# HUB-USB.net
KiCad netlist of a schematic drawn in Altium Designer
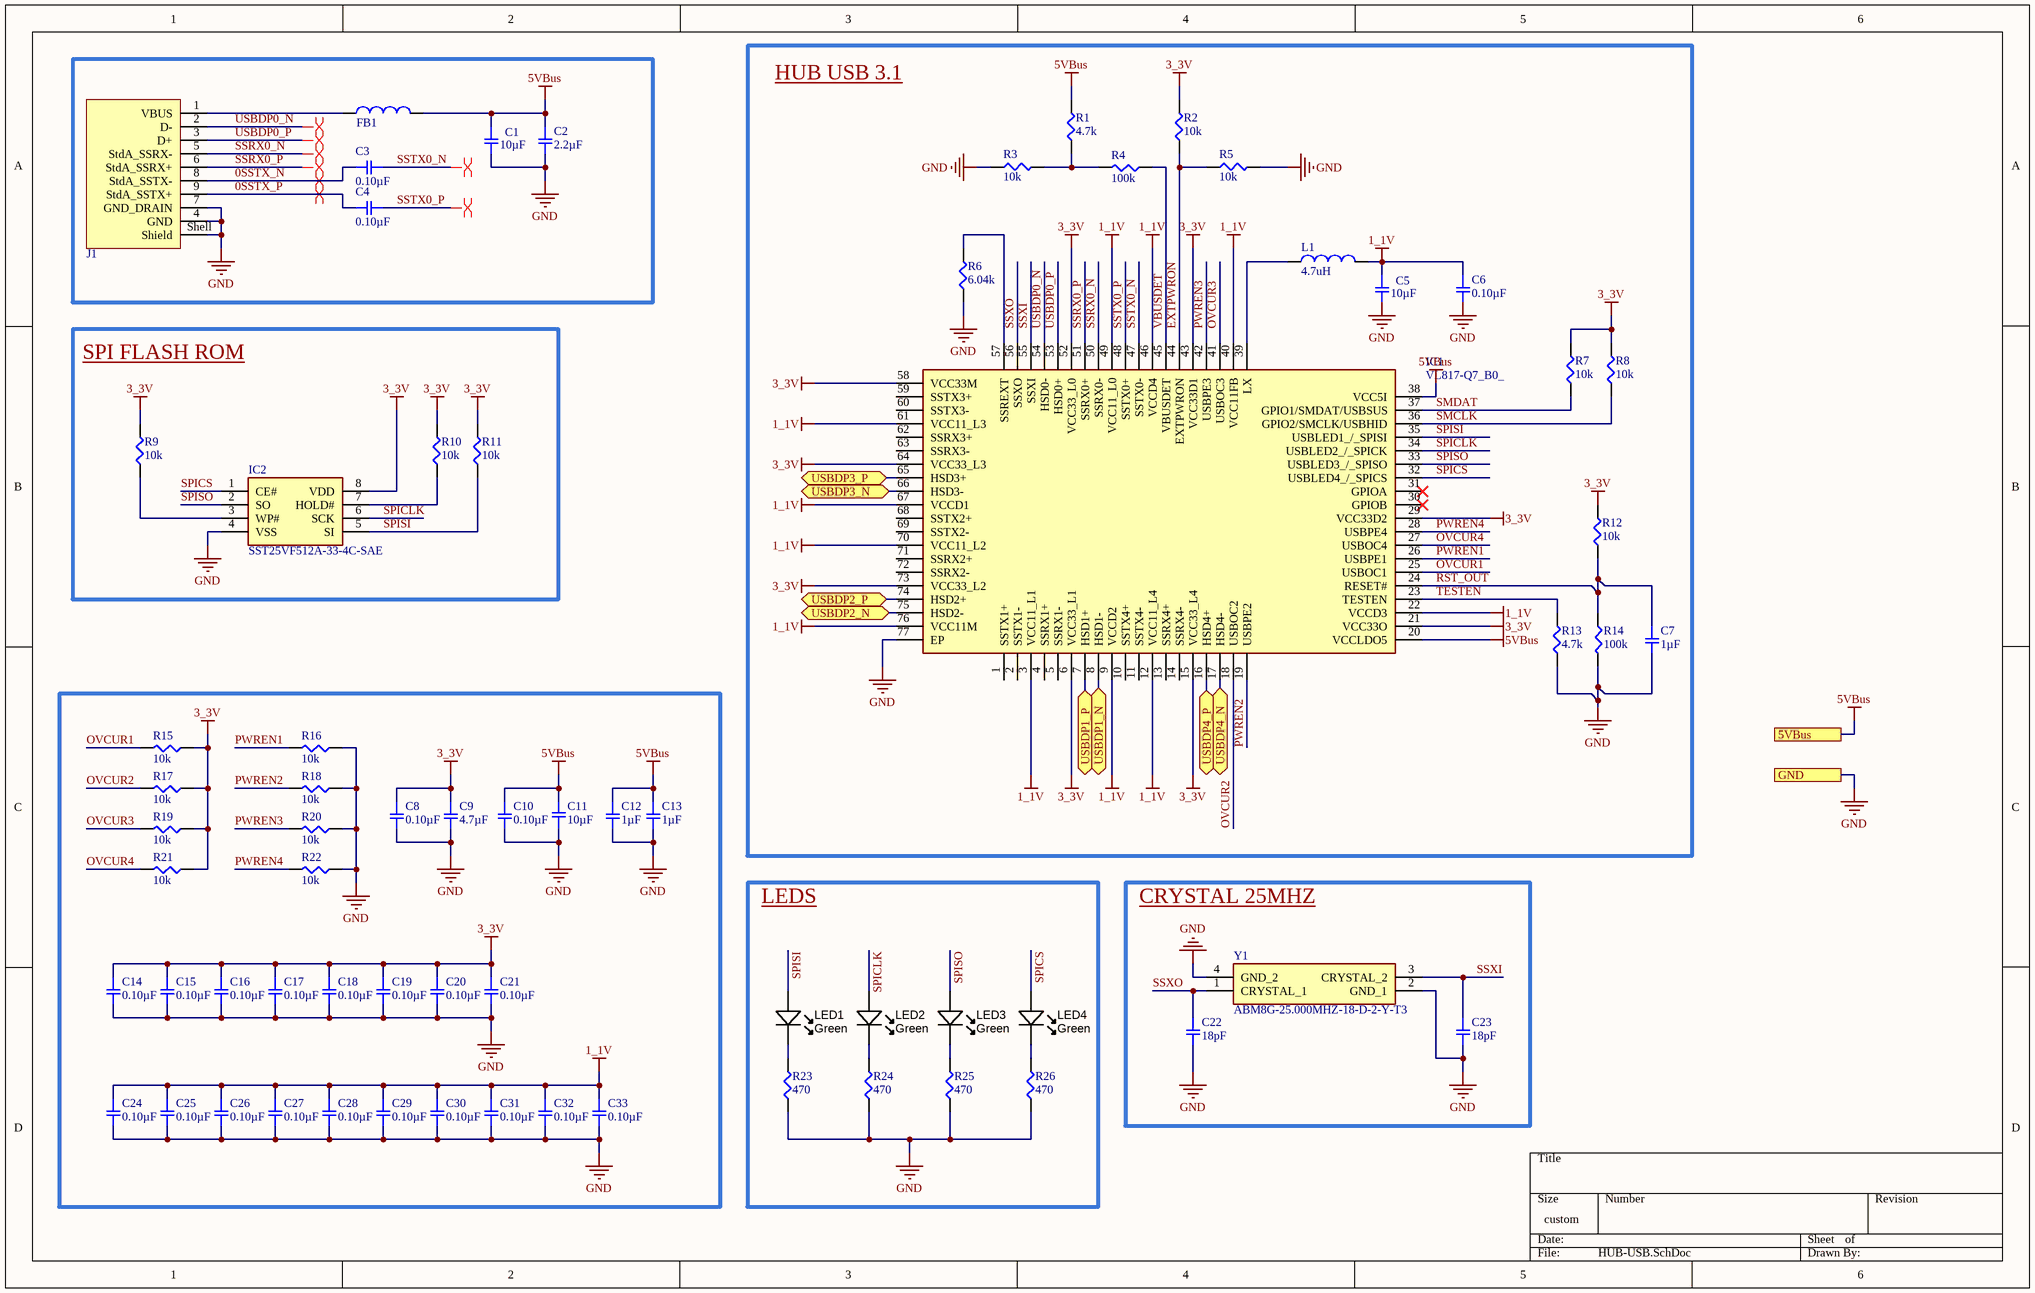
[diagram p0: HUB-USB.SchDoc]

(export (version "E")
  (design (tool "Eeschema 10.0.6"))
  (components
    (comp (ref "C1")
      (value "10µF")
      (footprint "SMD-0603C")
      (description "CAP CER 10UF 16V X6S 0603")
      (fields
        (field (name "PART NUMBER") "GRT188C81C106ME13D")
        (field (name "DIGI-KEY PART NUMBER") "490-12286-1-ND")
      )
      (libsource (lib "cap_murata") (part "CAPACITOR"))
    )
    (comp (ref "C2")
      (value "2.2µF")
      (footprint "SMD-0603C")
      (description "CAP CER 2.2UF 16V X6S 0603")
      (fields
        (field (name "PART NUMBER") "GRT188C81C225KE13D")
        (field (name "DIGI-KEY PART NUMBER") "490-12287-1-ND")
      )
      (libsource (lib "cap_murata") (part "CAPACITOR"))
    )
    (comp (ref "C3")
      (value "0.10µF")
      (footprint "SMD-0402C")
      (description "CAP CER 0.1UF 16V X7R 0402")
      (fields
        (field (name "PART NUMBER") "GCM155R71C104KA55J")
        (field (name "DIGI-KEY PART NUMBER") "490-7998-1-ND")
      )
      (libsource (lib "cap_murata") (part "CAPACITOR"))
    )
    (comp (ref "C4")
      (value "0.10µF")
      (footprint "SMD-0402C")
      (description "CAP CER 0.1UF 16V X7R 0402")
      (fields
        (field (name "PART NUMBER") "GCM155R71C104KA55J")
        (field (name "DIGI-KEY PART NUMBER") "490-7998-1-ND")
      )
      (libsource (lib "cap_murata") (part "CAPACITOR"))
    )
    (comp (ref "C5")
      (value "10µF")
      (footprint "SMD-0603C")
      (description "CAP CER 10UF 16V X6S 0603")
      (fields
        (field (name "PART NUMBER") "GRT188C81C106ME13D")
        (field (name "DIGI-KEY PART NUMBER") "490-12286-1-ND")
      )
      (libsource (lib "cap_murata") (part "CAPACITOR"))
    )
    (comp (ref "C6")
      (value "0.10µF")
      (footprint "SMD-0402C")
      (description "CAP CER 0.1UF 16V X7R 0402")
      (fields
        (field (name "PART NUMBER") "GCM155R71C104KA55J")
        (field (name "DIGI-KEY PART NUMBER") "490-7998-1-ND")
      )
      (libsource (lib "cap_murata") (part "CAPACITOR"))
    )
    (comp (ref "C7")
      (value "1µF")
      (footprint "SMD-0402C")
      (description "CAP CER 1UF 25V X5R 0402")
      (fields
        (field (name "PART NUMBER") "GRM155R61E105MA12D")
        (field (name "DIGI-KEY PART NUMBER") "490-10018-1-ND")
      )
      (libsource (lib "cap_murata") (part "CAPACITOR"))
    )
    (comp (ref "C8")
      (value "0.10µF")
      (footprint "SMD-0402C")
      (description "CAP CER 0.1UF 16V X7R 0402")
      (fields
        (field (name "PART NUMBER") "GCM155R71C104KA55J")
        (field (name "DIGI-KEY PART NUMBER") "490-7998-1-ND")
      )
      (libsource (lib "cap_murata") (part "CAPACITOR"))
    )
    (comp (ref "C9")
      (value "4.7µF")
      (footprint "SMD-0402C")
      (description "CAP CER 4.7UF 10V X5R 0402")
      (fields
        (field (name "PART NUMBER") "ZRB15XR61A475KE01D")
        (field (name "DIGI-KEY PART NUMBER") "490-13252-1-ND")
      )
      (libsource (lib "cap_murata") (part "CAPACITOR"))
    )
    (comp (ref "C10")
      (value "0.10µF")
      (footprint "SMD-0402C")
      (description "CAP CER 0.1UF 16V X7R 0402")
      (fields
        (field (name "PART NUMBER") "GCM155R71C104KA55J")
        (field (name "DIGI-KEY PART NUMBER") "490-7998-1-ND")
      )
      (libsource (lib "cap_murata") (part "CAPACITOR"))
    )
    (comp (ref "C11")
      (value "10µF")
      (footprint "SMD-0805C")
      (description "CAP CER 10UF 16V X6S 0805")
      (fields
        (field (name "PART NUMBER") "GRT21BC81C106KE01L")
        (field (name "DIGI-KEY PART NUMBER") "490-12343-1-ND")
      )
      (libsource (lib "cap_murata") (part "CAPACITOR"))
    )
    (comp (ref "C12")
      (value "1µF")
      (footprint "SMD-0402C")
      (description "CAP CER 1UF 25V X5R 0402")
      (fields
        (field (name "PART NUMBER") "GRM155R61E105MA12D")
        (field (name "DIGI-KEY PART NUMBER") "490-10018-1-ND")
      )
      (libsource (lib "cap_murata") (part "CAPACITOR"))
    )
    (comp (ref "C13")
      (value "1µF")
      (footprint "SMD-0402C")
      (description "CAP CER 1UF 25V X5R 0402")
      (fields
        (field (name "PART NUMBER") "GRM155R61E105MA12D")
        (field (name "DIGI-KEY PART NUMBER") "490-10018-1-ND")
      )
      (libsource (lib "cap_murata") (part "CAPACITOR"))
    )
    (comp (ref "C14")
      (value "0.10µF")
      (footprint "SMD-0402C")
      (description "CAP CER 0.1UF 16V X7R 0402")
      (fields
        (field (name "PART NUMBER") "GCM155R71C104KA55J")
        (field (name "DIGI-KEY PART NUMBER") "490-7998-1-ND")
      )
      (libsource (lib "cap_murata") (part "CAPACITOR"))
    )
    (comp (ref "C15")
      (value "0.10µF")
      (footprint "SMD-0402C")
      (description "CAP CER 0.1UF 16V X7R 0402")
      (fields
        (field (name "PART NUMBER") "GCM155R71C104KA55J")
        (field (name "DIGI-KEY PART NUMBER") "490-7998-1-ND")
      )
      (libsource (lib "cap_murata") (part "CAPACITOR"))
    )
    (comp (ref "C16")
      (value "0.10µF")
      (footprint "SMD-0402C")
      (description "CAP CER 0.1UF 16V X7R 0402")
      (fields
        (field (name "PART NUMBER") "GCM155R71C104KA55J")
        (field (name "DIGI-KEY PART NUMBER") "490-7998-1-ND")
      )
      (libsource (lib "cap_murata") (part "CAPACITOR"))
    )
    (comp (ref "C17")
      (value "0.10µF")
      (footprint "SMD-0402C")
      (description "CAP CER 0.1UF 16V X7R 0402")
      (fields
        (field (name "PART NUMBER") "GCM155R71C104KA55J")
        (field (name "DIGI-KEY PART NUMBER") "490-7998-1-ND")
      )
      (libsource (lib "cap_murata") (part "CAPACITOR"))
    )
    (comp (ref "C18")
      (value "0.10µF")
      (footprint "SMD-0402C")
      (description "CAP CER 0.1UF 16V X7R 0402")
      (fields
        (field (name "PART NUMBER") "GCM155R71C104KA55J")
        (field (name "DIGI-KEY PART NUMBER") "490-7998-1-ND")
      )
      (libsource (lib "cap_murata") (part "CAPACITOR"))
    )
    (comp (ref "C19")
      (value "0.10µF")
      (footprint "SMD-0402C")
      (description "CAP CER 0.1UF 16V X7R 0402")
      (fields
        (field (name "PART NUMBER") "GCM155R71C104KA55J")
        (field (name "DIGI-KEY PART NUMBER") "490-7998-1-ND")
      )
      (libsource (lib "cap_murata") (part "CAPACITOR"))
    )
    (comp (ref "C20")
      (value "0.10µF")
      (footprint "SMD-0402C")
      (description "CAP CER 0.1UF 16V X7R 0402")
      (fields
        (field (name "PART NUMBER") "GCM155R71C104KA55J")
        (field (name "DIGI-KEY PART NUMBER") "490-7998-1-ND")
      )
      (libsource (lib "cap_murata") (part "CAPACITOR"))
    )
    (comp (ref "C21")
      (value "0.10µF")
      (footprint "SMD-0402C")
      (description "CAP CER 0.1UF 16V X7R 0402")
      (fields
        (field (name "PART NUMBER") "GCM155R71C104KA55J")
        (field (name "DIGI-KEY PART NUMBER") "490-7998-1-ND")
      )
      (libsource (lib "cap_murata") (part "CAPACITOR"))
    )
    (comp (ref "C22")
      (value "18pF")
      (footprint "SMD-0402C")
      (description "CAP CER 18PF 25V NP0 0402")
      (fields
        (field (name "PART NUMBER") "GRM1555C1E180JA01D")
        (field (name "DIGI-KEY PART NUMBER") "490-6172-1-ND")
      )
      (libsource (lib "cap_murata") (part "CAPACITOR"))
    )
    (comp (ref "C23")
      (value "18pF")
      (footprint "SMD-0402C")
      (description "CAP CER 18PF 25V NP0 0402")
      (fields
        (field (name "PART NUMBER") "GRM1555C1E180JA01D")
        (field (name "DIGI-KEY PART NUMBER") "490-6172-1-ND")
      )
      (libsource (lib "cap_murata") (part "CAPACITOR"))
    )
    (comp (ref "C24")
      (value "0.10µF")
      (footprint "SMD-0402C")
      (description "CAP CER 0.1UF 16V X7R 0402")
      (fields
        (field (name "PART NUMBER") "GCM155R71C104KA55J")
        (field (name "DIGI-KEY PART NUMBER") "490-7998-1-ND")
      )
      (libsource (lib "cap_murata") (part "CAPACITOR"))
    )
    (comp (ref "C25")
      (value "0.10µF")
      (footprint "SMD-0402C")
      (description "CAP CER 0.1UF 16V X7R 0402")
      (fields
        (field (name "PART NUMBER") "GCM155R71C104KA55J")
        (field (name "DIGI-KEY PART NUMBER") "490-7998-1-ND")
      )
      (libsource (lib "cap_murata") (part "CAPACITOR"))
    )
    (comp (ref "C26")
      (value "0.10µF")
      (footprint "SMD-0402C")
      (description "CAP CER 0.1UF 16V X7R 0402")
      (fields
        (field (name "PART NUMBER") "GCM155R71C104KA55J")
        (field (name "DIGI-KEY PART NUMBER") "490-7998-1-ND")
      )
      (libsource (lib "cap_murata") (part "CAPACITOR"))
    )
    (comp (ref "C27")
      (value "0.10µF")
      (footprint "SMD-0402C")
      (description "CAP CER 0.1UF 16V X7R 0402")
      (fields
        (field (name "PART NUMBER") "GCM155R71C104KA55J")
        (field (name "DIGI-KEY PART NUMBER") "490-7998-1-ND")
      )
      (libsource (lib "cap_murata") (part "CAPACITOR"))
    )
    (comp (ref "C28")
      (value "0.10µF")
      (footprint "SMD-0402C")
      (description "CAP CER 0.1UF 16V X7R 0402")
      (fields
        (field (name "PART NUMBER") "GCM155R71C104KA55J")
        (field (name "DIGI-KEY PART NUMBER") "490-7998-1-ND")
      )
      (libsource (lib "cap_murata") (part "CAPACITOR"))
    )
    (comp (ref "C29")
      (value "0.10µF")
      (footprint "SMD-0402C")
      (description "CAP CER 0.1UF 16V X7R 0402")
      (fields
        (field (name "PART NUMBER") "GCM155R71C104KA55J")
        (field (name "DIGI-KEY PART NUMBER") "490-7998-1-ND")
      )
      (libsource (lib "cap_murata") (part "CAPACITOR"))
    )
    (comp (ref "C30")
      (value "0.10µF")
      (footprint "SMD-0402C")
      (description "CAP CER 0.1UF 16V X7R 0402")
      (fields
        (field (name "PART NUMBER") "GCM155R71C104KA55J")
        (field (name "DIGI-KEY PART NUMBER") "490-7998-1-ND")
      )
      (libsource (lib "cap_murata") (part "CAPACITOR"))
    )
    (comp (ref "C31")
      (value "0.10µF")
      (footprint "SMD-0402C")
      (description "CAP CER 0.1UF 16V X7R 0402")
      (fields
        (field (name "PART NUMBER") "GCM155R71C104KA55J")
        (field (name "DIGI-KEY PART NUMBER") "490-7998-1-ND")
      )
      (libsource (lib "cap_murata") (part "CAPACITOR"))
    )
    (comp (ref "C32")
      (value "0.10µF")
      (footprint "SMD-0402C")
      (description "CAP CER 0.1UF 16V X7R 0402")
      (fields
        (field (name "PART NUMBER") "GCM155R71C104KA55J")
        (field (name "DIGI-KEY PART NUMBER") "490-7998-1-ND")
      )
      (libsource (lib "cap_murata") (part "CAPACITOR"))
    )
    (comp (ref "C33")
      (value "0.10µF")
      (footprint "SMD-0402C")
      (description "CAP CER 0.1UF 16V X7R 0402")
      (fields
        (field (name "PART NUMBER") "GCM155R71C104KA55J")
        (field (name "DIGI-KEY PART NUMBER") "490-7998-1-ND")
      )
      (libsource (lib "cap_murata") (part "CAPACITOR"))
    )
    (comp (ref "FB1")
      (value "10Ohm")
      (footprint "WE-CBA_0402_L1W0.5H0.5_HC")
      (description "WE-CBA SMT EMI Suppression Ferrite Bead, size 0402, 10Ohm, 1.5A")
      (fields
        (field (name "MANUFACTURER PART NUMBER") "782423100")
        (field (name "MANUFACTURER") "Wurth Elektronik")
      )
      (libsource (lib "Altium_WE-CBA (rev22d)") (part "782423100"))
    )
    (comp (ref "IC1")
      (value "VL817-Q7_B0_")
      (footprint "SamacSys:QFN40P900X900X90-77N-D")
      (description "Integrated Circuit")
      (fields (field (name "MANUFACTURER_PART_NUMBER") "VL817-Q7(B0)"))
      (libsource (lib "SamacSys") (part "VL817-Q7_B0_"))
    )
    (comp (ref "IC2")
      (value "SST25VF512A-33-4C-SAE")
      (footprint "SamacSys:SOIC127P600X175-8N")
      (description "Integrated Circuit")
      (fields (field (name "MOUSER PART NUMBER") "804-25VF512A3CSAE"))
      (libsource (lib "SamacSys") (part "SST25VF512A-33-4C-SAE"))
    )
    (comp (ref "J1")
      (value "692122030100")
      (footprint "692122030100")
      (description "WR-COM USB 3.0 Type A Horizontal SMT")
      (fields (field (name "MANUFACTURER") "Wurth Elektronik"))
      (libsource (lib "Altium_WR-USB (rev23b)") (part "692122030100"))
    )
    (comp (ref "L1")
      (value "4.7uH")
      (footprint "INDC2518X200N")
      (description "Ind Power Chip Wirewound 4.7uH 20% 7.96MHz Ferrite 1.1A 1007 T/R")
      (fields (field (name "MP") "CB2518T4R7M"))
      (libsource (lib "DSD_Aerobits_RPI4_OLED") (part "CB2518T4R7M"))
    )
    (comp (ref "LED1")
      (value "Green")
      (footprint "LED-0603-GREEN")
      (description "LED 0603 SMD Green 525nm 350mcd 20mA")
      (libsource (lib "PBL - Light Sources") (part "LED_SMD_Green_0603_525nm_350mcd"))
    )
    (comp (ref "LED2")
      (value "Green")
      (footprint "LED-0603-GREEN")
      (description "LED 0603 SMD Green 525nm 350mcd 20mA")
      (libsource (lib "PBL - Light Sources") (part "LED_SMD_Green_0603_525nm_350mcd"))
    )
    (comp (ref "LED3")
      (value "Green")
      (footprint "LED-0603-GREEN")
      (description "LED 0603 SMD Green 525nm 350mcd 20mA")
      (libsource (lib "PBL - Light Sources") (part "LED_SMD_Green_0603_525nm_350mcd"))
    )
    (comp (ref "LED4")
      (value "Green")
      (footprint "LED-0603-GREEN")
      (description "LED 0603 SMD Green 525nm 350mcd 20mA")
      (libsource (lib "PBL - Light Sources") (part "LED_SMD_Green_0603_525nm_350mcd"))
    )
    (comp (ref "R1")
      (value "4.7k")
      (footprint "SMD-0402-RES")
      (description "RES SMD 4.7K OHM 1% 1/10W 0402")
      (fields
        (field (name "PART NUMBER") "ERJ-2RKF4701X")
        (field (name "DIGI-KEY PART NUMBER") "P4.70KLCT-ND")
      )
      (libsource (lib "res_panasonic_erj_xls") (part "RESISTOR"))
    )
    (comp (ref "R2")
      (value "10k")
      (footprint "SMD-0402-RES")
      (description "RES SMD 10K OHM 1% 1/10W 0402")
      (fields
        (field (name "PART NUMBER") "ERJ-2RKF1002X")
        (field (name "DIGI-KEY PART NUMBER") "P10.0KLCT-ND")
      )
      (libsource (lib "res_panasonic_erj_xls") (part "RESISTOR"))
    )
    (comp (ref "R3")
      (value "10k")
      (footprint "SMD-0402-RES")
      (description "RES SMD 10K OHM 1% 1/10W 0402")
      (fields
        (field (name "PART NUMBER") "ERJ-2RKF1002X")
        (field (name "DIGI-KEY PART NUMBER") "P10.0KLCT-ND")
      )
      (libsource (lib "res_panasonic_erj_xls") (part "RESISTOR"))
    )
    (comp (ref "R4")
      (value "100k")
      (footprint "SMD-0402-RES")
      (description "RES SMD 100K OHM 1% 1/10W 0402")
      (fields
        (field (name "PART NUMBER") "ERJ-2RKF1003X")
        (field (name "DIGI-KEY PART NUMBER") "P100KLCT-ND")
      )
      (libsource (lib "res_panasonic_erj_xls") (part "RESISTOR"))
    )
    (comp (ref "R5")
      (value "10k")
      (footprint "SMD-0402-RES")
      (description "RES SMD 10K OHM 1% 1/10W 0402")
      (fields
        (field (name "PART NUMBER") "ERJ-2RKF1002X")
        (field (name "DIGI-KEY PART NUMBER") "P10.0KLCT-ND")
      )
      (libsource (lib "res_panasonic_erj_xls") (part "RESISTOR"))
    )
    (comp (ref "R6")
      (value "6.04k")
      (footprint "SMD-0402-RES")
      (description "RES SMD 6.04K OHM 1% 1/10W 0402")
      (fields
        (field (name "PART NUMBER") "ERJ-2RKF6041X")
        (field (name "DIGI-KEY PART NUMBER") "P6.04KLCT-ND")
      )
      (libsource (lib "res_panasonic_erj_xls") (part "RESISTOR"))
    )
    (comp (ref "R7")
      (value "10k")
      (footprint "SMD-0402-RES")
      (description "RES SMD 10K OHM 1% 1/10W 0402")
      (fields
        (field (name "PART NUMBER") "ERJ-2RKF1002X")
        (field (name "DIGI-KEY PART NUMBER") "P10.0KLCT-ND")
      )
      (libsource (lib "res_panasonic_erj_xls") (part "RESISTOR"))
    )
    (comp (ref "R8")
      (value "10k")
      (footprint "SMD-0402-RES")
      (description "RES SMD 10K OHM 1% 1/10W 0402")
      (fields
        (field (name "PART NUMBER") "ERJ-2RKF1002X")
        (field (name "DIGI-KEY PART NUMBER") "P10.0KLCT-ND")
      )
      (libsource (lib "res_panasonic_erj_xls") (part "RESISTOR"))
    )
    (comp (ref "R9")
      (value "10k")
      (footprint "SMD-0402-RES")
      (description "RES SMD 10K OHM 1% 1/10W 0402")
      (fields
        (field (name "PART NUMBER") "ERJ-2RKF1002X")
        (field (name "DIGI-KEY PART NUMBER") "P10.0KLCT-ND")
      )
      (libsource (lib "res_panasonic_erj_xls") (part "RESISTOR"))
    )
    (comp (ref "R10")
      (value "10k")
      (footprint "SMD-0402-RES")
      (description "RES SMD 10K OHM 1% 1/10W 0402")
      (fields
        (field (name "PART NUMBER") "ERJ-2RKF1002X")
        (field (name "DIGI-KEY PART NUMBER") "P10.0KLCT-ND")
      )
      (libsource (lib "res_panasonic_erj_xls") (part "RESISTOR"))
    )
    (comp (ref "R11")
      (value "10k")
      (footprint "SMD-0402-RES")
      (description "RES SMD 10K OHM 1% 1/10W 0402")
      (fields
        (field (name "PART NUMBER") "ERJ-2RKF1002X")
        (field (name "DIGI-KEY PART NUMBER") "P10.0KLCT-ND")
      )
      (libsource (lib "res_panasonic_erj_xls") (part "RESISTOR"))
    )
    (comp (ref "R12")
      (value "10k")
      (footprint "SMD-0402-RES")
      (description "RES SMD 10K OHM 1% 1/10W 0402")
      (fields
        (field (name "PART NUMBER") "ERJ-2RKF1002X")
        (field (name "DIGI-KEY PART NUMBER") "P10.0KLCT-ND")
      )
      (libsource (lib "res_panasonic_erj_xls") (part "RESISTOR"))
    )
    (comp (ref "R13")
      (value "4.7k")
      (footprint "SMD-0402-RES")
      (description "RES SMD 4.7K OHM 1% 1/10W 0402")
      (fields
        (field (name "PART NUMBER") "ERJ-2RKF4701X")
        (field (name "DIGI-KEY PART NUMBER") "P4.70KLCT-ND")
      )
      (libsource (lib "res_panasonic_erj_xls") (part "RESISTOR"))
    )
    (comp (ref "R14")
      (value "100k")
      (footprint "SMD-0402-RES")
      (description "RES SMD 100K OHM 1% 1/10W 0402")
      (fields
        (field (name "PART NUMBER") "ERJ-2RKF1003X")
        (field (name "DIGI-KEY PART NUMBER") "P100KLCT-ND")
      )
      (libsource (lib "res_panasonic_erj_xls") (part "RESISTOR"))
    )
    (comp (ref "R15")
      (value "10k")
      (footprint "SMD-0402-RES")
      (description "RES SMD 10K OHM 1% 1/10W 0402")
      (fields
        (field (name "PART NUMBER") "ERJ-2RKF1002X")
        (field (name "DIGI-KEY PART NUMBER") "P10.0KLCT-ND")
      )
      (libsource (lib "res_panasonic_erj_xls") (part "RESISTOR"))
    )
    (comp (ref "R16")
      (value "10k")
      (footprint "SMD-0402-RES")
      (description "RES SMD 10K OHM 1% 1/10W 0402")
      (fields
        (field (name "PART NUMBER") "ERJ-2RKF1002X")
        (field (name "DIGI-KEY PART NUMBER") "P10.0KLCT-ND")
      )
      (libsource (lib "res_panasonic_erj_xls") (part "RESISTOR"))
    )
    (comp (ref "R17")
      (value "10k")
      (footprint "SMD-0402-RES")
      (description "RES SMD 10K OHM 1% 1/10W 0402")
      (fields
        (field (name "PART NUMBER") "ERJ-2RKF1002X")
        (field (name "DIGI-KEY PART NUMBER") "P10.0KLCT-ND")
      )
      (libsource (lib "res_panasonic_erj_xls") (part "RESISTOR"))
    )
    (comp (ref "R18")
      (value "10k")
      (footprint "SMD-0402-RES")
      (description "RES SMD 10K OHM 1% 1/10W 0402")
      (fields
        (field (name "PART NUMBER") "ERJ-2RKF1002X")
        (field (name "DIGI-KEY PART NUMBER") "P10.0KLCT-ND")
      )
      (libsource (lib "res_panasonic_erj_xls") (part "RESISTOR"))
    )
    (comp (ref "R19")
      (value "10k")
      (footprint "SMD-0402-RES")
      (description "RES SMD 10K OHM 1% 1/10W 0402")
      (fields
        (field (name "PART NUMBER") "ERJ-2RKF1002X")
        (field (name "DIGI-KEY PART NUMBER") "P10.0KLCT-ND")
      )
      (libsource (lib "res_panasonic_erj_xls") (part "RESISTOR"))
    )
    (comp (ref "R20")
      (value "10k")
      (footprint "SMD-0402-RES")
      (description "RES SMD 10K OHM 1% 1/10W 0402")
      (fields
        (field (name "PART NUMBER") "ERJ-2RKF1002X")
        (field (name "DIGI-KEY PART NUMBER") "P10.0KLCT-ND")
      )
      (libsource (lib "res_panasonic_erj_xls") (part "RESISTOR"))
    )
    (comp (ref "R21")
      (value "10k")
      (footprint "SMD-0402-RES")
      (description "RES SMD 10K OHM 1% 1/10W 0402")
      (fields
        (field (name "PART NUMBER") "ERJ-2RKF1002X")
        (field (name "DIGI-KEY PART NUMBER") "P10.0KLCT-ND")
      )
      (libsource (lib "res_panasonic_erj_xls") (part "RESISTOR"))
    )
    (comp (ref "R22")
      (value "10k")
      (footprint "SMD-0402-RES")
      (description "RES SMD 10K OHM 1% 1/10W 0402")
      (fields
        (field (name "PART NUMBER") "ERJ-2RKF1002X")
        (field (name "DIGI-KEY PART NUMBER") "P10.0KLCT-ND")
      )
      (libsource (lib "res_panasonic_erj_xls") (part "RESISTOR"))
    )
    (comp (ref "R23")
      (value "470")
      (footprint "SMD-0402-RES")
      (description "RES SMD 470 OHM 5% 1/10W 0402")
      (fields (field (name "PART NUMBER") "ERJ-2GEJ471X") (field (name "DIGI-KEY PART NUMBER") "P470JCT-ND"))
      (libsource (lib "res_panasonic_erj_xls") (part "RESISTOR"))
    )
    (comp (ref "R24")
      (value "470")
      (footprint "SMD-0402-RES")
      (description "RES SMD 470 OHM 5% 1/10W 0402")
      (fields (field (name "PART NUMBER") "ERJ-2GEJ471X") (field (name "DIGI-KEY PART NUMBER") "P470JCT-ND"))
      (libsource (lib "res_panasonic_erj_xls") (part "RESISTOR"))
    )
    (comp (ref "R25")
      (value "470")
      (footprint "SMD-0402-RES")
      (description "RES SMD 470 OHM 5% 1/10W 0402")
      (fields (field (name "PART NUMBER") "ERJ-2GEJ471X") (field (name "DIGI-KEY PART NUMBER") "P470JCT-ND"))
      (libsource (lib "res_panasonic_erj_xls") (part "RESISTOR"))
    )
    (comp (ref "R26")
      (value "470")
      (footprint "SMD-0402-RES")
      (description "RES SMD 470 OHM 5% 1/10W 0402")
      (fields (field (name "PART NUMBER") "ERJ-2GEJ471X") (field (name "DIGI-KEY PART NUMBER") "P470JCT-ND"))
      (libsource (lib "res_panasonic_erj_xls") (part "RESISTOR"))
    )
    (comp (ref "Y1")
      (value "ABM8G-25.000MHZ-18-D-2-Y-T3")
      (footprint "SamacSys:ABM8G16000MHZB4YT")
      (description "Crystal or Oscillator")
      (libsource (lib "SamacSys") (part "ABM8G-25.000MHZ-18-D-2-Y-T3"))
    )
  )
  (nets
    (net (code "1") (name "/0SSTX_N") (class "Default")
      (node (ref "C3") (pin "2") (pinfunction "2_2") (pintype "passive"))
      (node (ref "J1") (pin "8") (pinfunction "StdA_SSTX-_8") (pintype "passive"))
    )
    (net (code "2") (name "/0SSTX_P") (class "Default")
      (node (ref "C4") (pin "2") (pinfunction "2_2") (pintype "passive"))
      (node (ref "J1") (pin "9") (pinfunction "StdA_SSTX+_9") (pintype "passive"))
    )
    (net (code "3") (name "/EXTPWRON") (class "Default")
      (node (ref "IC1") (pin "44") (pinfunction "EXTPWRON_44") (pintype "passive"))
      (node (ref "R2") (pin "1") (pinfunction "1_1") (pintype "passive"))
      (node (ref "R5") (pin "1") (pinfunction "1_1") (pintype "passive"))
    )
    (net (code "4") (name "/OVCUR1") (class "Default")
      (node (ref "IC1") (pin "25") (pinfunction "USBOC1_25") (pintype "passive"))
      (node (ref "R15") (pin "2") (pinfunction "2_2") (pintype "passive"))
    )
    (net (code "5") (name "/OVCUR2") (class "Default")
      (node (ref "IC1") (pin "18") (pinfunction "USBOC2_18") (pintype "passive"))
      (node (ref "R17") (pin "2") (pinfunction "2_2") (pintype "passive"))
    )
    (net (code "6") (name "/OVCUR3") (class "Default")
      (node (ref "IC1") (pin "41") (pinfunction "USBOC3_41") (pintype "passive"))
      (node (ref "R19") (pin "2") (pinfunction "2_2") (pintype "passive"))
    )
    (net (code "7") (name "/OVCUR4") (class "Default")
      (node (ref "IC1") (pin "27") (pinfunction "USBOC4_27") (pintype "passive"))
      (node (ref "R21") (pin "2") (pinfunction "2_2") (pintype "passive"))
    )
    (net (code "8") (name "/PWREN1") (class "Default")
      (node (ref "IC1") (pin "26") (pinfunction "USBPE1_26") (pintype "passive"))
      (node (ref "R16") (pin "2") (pinfunction "2_2") (pintype "passive"))
    )
    (net (code "9") (name "/PWREN2") (class "Default")
      (node (ref "IC1") (pin "19") (pinfunction "USBPE2_19") (pintype "passive"))
      (node (ref "R18") (pin "2") (pinfunction "2_2") (pintype "passive"))
    )
    (net (code "10") (name "/PWREN3") (class "Default")
      (node (ref "IC1") (pin "42") (pinfunction "USBPE3_42") (pintype "passive"))
      (node (ref "R20") (pin "2") (pinfunction "2_2") (pintype "passive"))
    )
    (net (code "11") (name "/PWREN4") (class "Default")
      (node (ref "IC1") (pin "28") (pinfunction "USBPE4_28") (pintype "passive"))
      (node (ref "R22") (pin "2") (pinfunction "2_2") (pintype "passive"))
    )
    (net (code "12") (name "/RST_OUT") (class "Default")
      (node (ref "C7") (pin "1") (pinfunction "1_1") (pintype "passive"))
      (node (ref "IC1") (pin "24") (pinfunction "RESET#_24") (pintype "passive"))
      (node (ref "R12") (pin "1") (pinfunction "1_1") (pintype "passive"))
      (node (ref "R14") (pin "1") (pinfunction "1_1") (pintype "passive"))
    )
    (net (code "13") (name "/SMCLK") (class "Default")
      (node (ref "IC1") (pin "36") (pinfunction "GPIO2/SMCLK/USBHID_36") (pintype "passive"))
      (node (ref "R8") (pin "1") (pinfunction "1_1") (pintype "passive"))
    )
    (net (code "14") (name "/SMDAT") (class "Default")
      (node (ref "IC1") (pin "37") (pinfunction "GPIO1/SMDAT/USBSUS_37") (pintype "passive"))
      (node (ref "R7") (pin "1") (pinfunction "1_1") (pintype "passive"))
    )
    (net (code "15") (name "/SPICLK") (class "Default")
      (node (ref "IC1") (pin "34") (pinfunction "USBLED2_/_SPICK_34") (pintype "passive"))
      (node (ref "IC2") (pin "6") (pinfunction "SCK_6") (pintype "passive"))
      (node (ref "LED2") (pin "A") (pinfunction "A_A") (pintype "passive"))
    )
    (net (code "16") (name "/SPICS") (class "Default")
      (node (ref "IC1") (pin "32") (pinfunction "USBLED4_/_SPICS_32") (pintype "passive"))
      (node (ref "IC2") (pin "1") (pinfunction "CE#_1") (pintype "passive"))
      (node (ref "LED4") (pin "A") (pinfunction "A_A") (pintype "passive"))
    )
    (net (code "17") (name "/SPISI") (class "Default")
      (node (ref "IC1") (pin "35") (pinfunction "USBLED1_/_SPISI_35") (pintype "passive"))
      (node (ref "IC2") (pin "5") (pinfunction "SI_5") (pintype "passive"))
      (node (ref "LED1") (pin "A") (pinfunction "A_A") (pintype "passive"))
      (node (ref "R11") (pin "1") (pinfunction "1_1") (pintype "passive"))
    )
    (net (code "18") (name "/SPISO") (class "Default")
      (node (ref "IC1") (pin "33") (pinfunction "USBLED3_/_SPISO_33") (pintype "passive"))
      (node (ref "IC2") (pin "2") (pinfunction "SO_2") (pintype "passive"))
      (node (ref "LED3") (pin "A") (pinfunction "A_A") (pintype "passive"))
    )
    (net (code "19") (name "/SSRX0_N") (class "Default")
      (node (ref "IC1") (pin "50") (pinfunction "SSRX0-_50") (pintype "passive"))
      (node (ref "J1") (pin "5") (pinfunction "StdA_SSRX-_5") (pintype "passive"))
    )
    (net (code "20") (name "/SSRX0_P") (class "Default")
      (node (ref "IC1") (pin "51") (pinfunction "SSRX0+_51") (pintype "passive"))
      (node (ref "J1") (pin "6") (pinfunction "StdA_SSRX+_6") (pintype "passive"))
    )
    (net (code "21") (name "/SSTX0_N") (class "Default")
      (node (ref "C3") (pin "1") (pinfunction "1_1") (pintype "passive"))
      (node (ref "IC1") (pin "47") (pinfunction "SSTX0-_47") (pintype "passive"))
    )
    (net (code "22") (name "/SSTX0_P") (class "Default")
      (node (ref "C4") (pin "1") (pinfunction "1_1") (pintype "passive"))
      (node (ref "IC1") (pin "48") (pinfunction "SSTX0+_48") (pintype "passive"))
    )
    (net (code "23") (name "/SSXI") (class "Default")
      (node (ref "C23") (pin "1") (pinfunction "1_1") (pintype "passive"))
      (node (ref "IC1") (pin "55") (pinfunction "SSXI_55") (pintype "passive"))
      (node (ref "Y1") (pin "3") (pinfunction "CRYSTAL_2_3") (pintype "passive"))
    )
    (net (code "24") (name "/SSXO") (class "Default")
      (node (ref "C22") (pin "1") (pinfunction "1_1") (pintype "passive"))
      (node (ref "IC1") (pin "56") (pinfunction "SSXO_56") (pintype "passive"))
      (node (ref "Y1") (pin "1") (pinfunction "CRYSTAL_1_1") (pintype "passive"))
    )
    (net (code "25") (name "/TESTEN") (class "Default")
      (node (ref "IC1") (pin "23") (pinfunction "TESTEN_23") (pintype "passive"))
      (node (ref "R13") (pin "2") (pinfunction "2_2") (pintype "passive"))
    )
    (net (code "26") (name "/USBDP0_N") (class "Default")
      (node (ref "IC1") (pin "54") (pinfunction "HSD0-_54") (pintype "passive"))
      (node (ref "J1") (pin "2") (pinfunction "D-_2") (pintype "passive"))
    )
    (net (code "27") (name "/USBDP0_P") (class "Default")
      (node (ref "IC1") (pin "53") (pinfunction "HSD0+_53") (pintype "passive"))
      (node (ref "J1") (pin "3") (pinfunction "D+_3") (pintype "passive"))
    )
    (net (code "28") (name "/USBDP1_N") (class "Default")
      (node (ref "IC1") (pin "8") (pinfunction "HSD1-_8") (pintype "passive"))
    )
    (net (code "29") (name "/USBDP1_P") (class "Default")
      (node (ref "IC1") (pin "7") (pinfunction "HSD1+_7") (pintype "passive"))
    )
    (net (code "30") (name "/USBDP2_N") (class "Default")
      (node (ref "IC1") (pin "75") (pinfunction "HSD2-_75") (pintype "passive"))
    )
    (net (code "31") (name "/USBDP2_P") (class "Default")
      (node (ref "IC1") (pin "74") (pinfunction "HSD2+_74") (pintype "passive"))
    )
    (net (code "32") (name "/USBDP3_N") (class "Default")
      (node (ref "IC1") (pin "66") (pinfunction "HSD3-_66") (pintype "passive"))
    )
    (net (code "33") (name "/USBDP3_P") (class "Default")
      (node (ref "IC1") (pin "65") (pinfunction "HSD3+_65") (pintype "passive"))
    )
    (net (code "34") (name "/USBDP4_N") (class "Default")
      (node (ref "IC1") (pin "17") (pinfunction "HSD4-_17") (pintype "passive"))
    )
    (net (code "35") (name "/USBDP4_P") (class "Default")
      (node (ref "IC1") (pin "16") (pinfunction "HSD4+_16") (pintype "passive"))
    )
    (net (code "36") (name "/VBUSDET") (class "Default")
      (node (ref "IC1") (pin "45") (pinfunction "VBUSDET_45") (pintype "passive"))
      (node (ref "R4") (pin "1") (pinfunction "1_1") (pintype "passive"))
    )
    (net (code "37") (name "1_1V") (class "Default")
      (node (ref "C24") (pin "1") (pinfunction "1_1") (pintype "passive"))
      (node (ref "C25") (pin "1") (pinfunction "1_1") (pintype "passive"))
      (node (ref "C26") (pin "1") (pinfunction "1_1") (pintype "passive"))
      (node (ref "C27") (pin "1") (pinfunction "1_1") (pintype "passive"))
      (node (ref "C28") (pin "1") (pinfunction "1_1") (pintype "passive"))
      (node (ref "C29") (pin "1") (pinfunction "1_1") (pintype "passive"))
      (node (ref "C30") (pin "1") (pinfunction "1_1") (pintype "passive"))
      (node (ref "C31") (pin "1") (pinfunction "1_1") (pintype "passive"))
      (node (ref "C32") (pin "1") (pinfunction "1_1") (pintype "passive"))
      (node (ref "C33") (pin "1") (pinfunction "1_1") (pintype "passive"))
      (node (ref "C5") (pin "1") (pinfunction "1_1") (pintype "passive"))
      (node (ref "C6") (pin "1") (pinfunction "1_1") (pintype "passive"))
      (node (ref "IC1") (pin "12") (pinfunction "VCC11_L4_12") (pintype "passive"))
      (node (ref "IC1") (pin "22") (pinfunction "VCCD3_22") (pintype "passive"))
      (node (ref "IC1") (pin "3") (pinfunction "VCC11_L1_3") (pintype "passive"))
      (node (ref "IC1") (pin "40") (pinfunction "VCC11FB_40") (pintype "passive"))
      (node (ref "IC1") (pin "46") (pinfunction "VCCD4_46") (pintype "passive"))
      (node (ref "IC1") (pin "49") (pinfunction "VCC11_L0_49") (pintype "passive"))
      (node (ref "IC1") (pin "61") (pinfunction "VCC11_L3_61") (pintype "passive"))
      (node (ref "IC1") (pin "67") (pinfunction "VCCD1_67") (pintype "passive"))
      (node (ref "IC1") (pin "70") (pinfunction "VCC11_L2_70") (pintype "passive"))
      (node (ref "IC1") (pin "76") (pinfunction "VCC11M_76") (pintype "passive"))
      (node (ref "IC1") (pin "9") (pinfunction "VCCD2_9") (pintype "passive"))
      (node (ref "L1") (pin "2") (pinfunction "2_2") (pintype "passive"))
    )
    (net (code "38") (name "3_3V") (class "Default")
      (node (ref "C14") (pin "1") (pinfunction "1_1") (pintype "passive"))
      (node (ref "C15") (pin "1") (pinfunction "1_1") (pintype "passive"))
      (node (ref "C16") (pin "1") (pinfunction "1_1") (pintype "passive"))
      (node (ref "C17") (pin "1") (pinfunction "1_1") (pintype "passive"))
      (node (ref "C18") (pin "1") (pinfunction "1_1") (pintype "passive"))
      (node (ref "C19") (pin "1") (pinfunction "1_1") (pintype "passive"))
      (node (ref "C20") (pin "1") (pinfunction "1_1") (pintype "passive"))
      (node (ref "C21") (pin "1") (pinfunction "1_1") (pintype "passive"))
      (node (ref "C8") (pin "1") (pinfunction "1_1") (pintype "passive"))
      (node (ref "C9") (pin "1") (pinfunction "1_1") (pintype "passive"))
      (node (ref "IC1") (pin "15") (pinfunction "VCC33_L4_15") (pintype "passive"))
      (node (ref "IC1") (pin "21") (pinfunction "VCC33O_21") (pintype "passive"))
      (node (ref "IC1") (pin "29") (pinfunction "VCC33D2_29") (pintype "passive"))
      (node (ref "IC1") (pin "43") (pinfunction "VCC33D1_43") (pintype "passive"))
      (node (ref "IC1") (pin "52") (pinfunction "VCC33_L0_52") (pintype "passive"))
      (node (ref "IC1") (pin "58") (pinfunction "VCC33M_58") (pintype "passive"))
      (node (ref "IC1") (pin "6") (pinfunction "VCC33_L1_6") (pintype "passive"))
      (node (ref "IC1") (pin "64") (pinfunction "VCC33_L3_64") (pintype "passive"))
      (node (ref "IC1") (pin "73") (pinfunction "VCC33_L2_73") (pintype "passive"))
      (node (ref "IC2") (pin "8") (pinfunction "VDD_8") (pintype "passive"))
      (node (ref "R10") (pin "2") (pinfunction "2_2") (pintype "passive"))
      (node (ref "R11") (pin "2") (pinfunction "2_2") (pintype "passive"))
      (node (ref "R12") (pin "2") (pinfunction "2_2") (pintype "passive"))
      (node (ref "R15") (pin "1") (pinfunction "1_1") (pintype "passive"))
      (node (ref "R17") (pin "1") (pinfunction "1_1") (pintype "passive"))
      (node (ref "R19") (pin "1") (pinfunction "1_1") (pintype "passive"))
      (node (ref "R2") (pin "2") (pinfunction "2_2") (pintype "passive"))
      (node (ref "R21") (pin "1") (pinfunction "1_1") (pintype "passive"))
      (node (ref "R7") (pin "2") (pinfunction "2_2") (pintype "passive"))
      (node (ref "R8") (pin "2") (pinfunction "2_2") (pintype "passive"))
      (node (ref "R9") (pin "2") (pinfunction "2_2") (pintype "passive"))
    )
    (net (code "39") (name "5VBus") (class "Default")
      (node (ref "C1") (pin "1") (pinfunction "1_1") (pintype "passive"))
      (node (ref "C10") (pin "1") (pinfunction "1_1") (pintype "passive"))
      (node (ref "C11") (pin "2") (pinfunction "2_2") (pintype "passive"))
      (node (ref "C12") (pin "1") (pinfunction "1_1") (pintype "passive"))
      (node (ref "C13") (pin "1") (pinfunction "1_1") (pintype "passive"))
      (node (ref "C2") (pin "1") (pinfunction "1_1") (pintype "passive"))
      (node (ref "FB1") (pin "2") (pinfunction "2_2") (pintype "passive"))
      (node (ref "IC1") (pin "20") (pinfunction "VCCLDO5_20") (pintype "passive"))
      (node (ref "IC1") (pin "38") (pinfunction "VCC5I_38") (pintype "passive"))
      (node (ref "R1") (pin "2") (pinfunction "2_2") (pintype "passive"))
    )
    (net (code "40") (name "GND") (class "Default")
      (node (ref "C1") (pin "2") (pinfunction "2_2") (pintype "passive"))
      (node (ref "C10") (pin "2") (pinfunction "2_2") (pintype "passive"))
      (node (ref "C11") (pin "1") (pinfunction "1_1") (pintype "passive"))
      (node (ref "C12") (pin "2") (pinfunction "2_2") (pintype "passive"))
      (node (ref "C13") (pin "2") (pinfunction "2_2") (pintype "passive"))
      (node (ref "C14") (pin "2") (pinfunction "2_2") (pintype "passive"))
      (node (ref "C15") (pin "2") (pinfunction "2_2") (pintype "passive"))
      (node (ref "C16") (pin "2") (pinfunction "2_2") (pintype "passive"))
      (node (ref "C17") (pin "2") (pinfunction "2_2") (pintype "passive"))
      (node (ref "C18") (pin "2") (pinfunction "2_2") (pintype "passive"))
      (node (ref "C19") (pin "2") (pinfunction "2_2") (pintype "passive"))
      (node (ref "C2") (pin "2") (pinfunction "2_2") (pintype "passive"))
      (node (ref "C20") (pin "2") (pinfunction "2_2") (pintype "passive"))
      (node (ref "C21") (pin "2") (pinfunction "2_2") (pintype "passive"))
      (node (ref "C22") (pin "2") (pinfunction "2_2") (pintype "passive"))
      (node (ref "C23") (pin "2") (pinfunction "2_2") (pintype "passive"))
      (node (ref "C24") (pin "2") (pinfunction "2_2") (pintype "passive"))
      (node (ref "C25") (pin "2") (pinfunction "2_2") (pintype "passive"))
      (node (ref "C26") (pin "2") (pinfunction "2_2") (pintype "passive"))
      (node (ref "C27") (pin "2") (pinfunction "2_2") (pintype "passive"))
      (node (ref "C28") (pin "2") (pinfunction "2_2") (pintype "passive"))
      (node (ref "C29") (pin "2") (pinfunction "2_2") (pintype "passive"))
      (node (ref "C30") (pin "2") (pinfunction "2_2") (pintype "passive"))
      (node (ref "C31") (pin "2") (pinfunction "2_2") (pintype "passive"))
      (node (ref "C32") (pin "2") (pinfunction "2_2") (pintype "passive"))
      (node (ref "C33") (pin "2") (pinfunction "2_2") (pintype "passive"))
      (node (ref "C5") (pin "2") (pinfunction "2_2") (pintype "passive"))
      (node (ref "C6") (pin "2") (pinfunction "2_2") (pintype "passive"))
      (node (ref "C7") (pin "2") (pinfunction "2_2") (pintype "passive"))
      (node (ref "C8") (pin "2") (pinfunction "2_2") (pintype "passive"))
      (node (ref "C9") (pin "2") (pinfunction "2_2") (pintype "passive"))
      (node (ref "IC1") (pin "77") (pinfunction "EP_77") (pintype "passive"))
      (node (ref "IC2") (pin "4") (pinfunction "VSS_4") (pintype "passive"))
      (node (ref "J1") (pin "4") (pinfunction "GND_4") (pintype "passive"))
      (node (ref "J1") (pin "7") (pinfunction "GND_DRAIN_7") (pintype "passive"))
      (node (ref "J1") (pin "Shell") (pinfunction "Shield_Shell") (pintype "passive"))
      (node (ref "R13") (pin "1") (pinfunction "1_1") (pintype "passive"))
      (node (ref "R14") (pin "2") (pinfunction "2_2") (pintype "passive"))
      (node (ref "R16") (pin "1") (pinfunction "1_1") (pintype "passive"))
      (node (ref "R18") (pin "1") (pinfunction "1_1") (pintype "passive"))
      (node (ref "R20") (pin "1") (pinfunction "1_1") (pintype "passive"))
      (node (ref "R22") (pin "1") (pinfunction "1_1") (pintype "passive"))
      (node (ref "R23") (pin "1") (pinfunction "1_1") (pintype "passive"))
      (node (ref "R24") (pin "1") (pinfunction "1_1") (pintype "passive"))
      (node (ref "R25") (pin "1") (pinfunction "1_1") (pintype "passive"))
      (node (ref "R26") (pin "1") (pinfunction "1_1") (pintype "passive"))
      (node (ref "R3") (pin "1") (pinfunction "1_1") (pintype "passive"))
      (node (ref "R5") (pin "2") (pinfunction "2_2") (pintype "passive"))
      (node (ref "R6") (pin "1") (pinfunction "1_1") (pintype "passive"))
      (node (ref "Y1") (pin "2") (pinfunction "GND_1_2") (pintype "passive"))
      (node (ref "Y1") (pin "4") (pinfunction "GND_2_4") (pintype "passive"))
    )
    (net (code "41") (name "Net-(IC1-LX)") (class "Default")
      (node (ref "IC1") (pin "39") (pinfunction "LX_39") (pintype "passive"))
      (node (ref "L1") (pin "1") (pinfunction "1_1") (pintype "passive"))
    )
    (net (code "42") (name "Net-(IC1-SSREXT)") (class "Default")
      (node (ref "IC1") (pin "57") (pinfunction "SSREXT_57") (pintype "passive"))
      (node (ref "R6") (pin "2") (pinfunction "2_2") (pintype "passive"))
    )
    (net (code "43") (name "Net-(IC2-HOLD#)") (class "Default")
      (node (ref "IC2") (pin "7") (pinfunction "HOLD#_7") (pintype "passive"))
      (node (ref "R10") (pin "1") (pinfunction "1_1") (pintype "passive"))
    )
    (net (code "44") (name "Net-(IC2-WP#)") (class "Default")
      (node (ref "IC2") (pin "3") (pinfunction "WP#_3") (pintype "passive"))
      (node (ref "R9") (pin "1") (pinfunction "1_1") (pintype "passive"))
    )
    (net (code "45") (name "Net-(J1-VBUS)") (class "Default")
      (node (ref "FB1") (pin "1") (pinfunction "1_1") (pintype "passive"))
      (node (ref "J1") (pin "1") (pinfunction "VBUS_1") (pintype "passive"))
    )
    (net (code "46") (name "Net-(LED1-PadK)") (class "Default")
      (node (ref "LED1") (pin "K") (pinfunction "K_K") (pintype "passive"))
      (node (ref "R23") (pin "2") (pinfunction "2_2") (pintype "passive"))
    )
    (net (code "47") (name "Net-(LED2-PadK)") (class "Default")
      (node (ref "LED2") (pin "K") (pinfunction "K_K") (pintype "passive"))
      (node (ref "R24") (pin "2") (pinfunction "2_2") (pintype "passive"))
    )
    (net (code "48") (name "Net-(LED3-PadK)") (class "Default")
      (node (ref "LED3") (pin "K") (pinfunction "K_K") (pintype "passive"))
      (node (ref "R25") (pin "2") (pinfunction "2_2") (pintype "passive"))
    )
    (net (code "49") (name "Net-(LED4-PadK)") (class "Default")
      (node (ref "LED4") (pin "K") (pinfunction "K_K") (pintype "passive"))
      (node (ref "R26") (pin "2") (pinfunction "2_2") (pintype "passive"))
    )
    (net (code "50") (name "Net-(R1-Pad1)") (class "Default")
      (node (ref "R1") (pin "1") (pinfunction "1_1") (pintype "passive"))
      (node (ref "R3") (pin "2") (pinfunction "2_2") (pintype "passive"))
      (node (ref "R4") (pin "2") (pinfunction "2_2") (pintype "passive"))
    )
    (net (code "51") (name "unconnected-(IC1-GPIOA-Pad31)") (class "Default")
      (node (ref "IC1") (pin "31") (pinfunction "GPIOA_31") (pintype "passive+no_connect"))
    )
    (net (code "52") (name "unconnected-(IC1-GPIOB-Pad30)") (class "Default")
      (node (ref "IC1") (pin "30") (pinfunction "GPIOB_30") (pintype "passive+no_connect"))
    )
    (net (code "53") (name "unconnected-(IC1-SSRX1+-Pad4)") (class "Default")
      (node (ref "IC1") (pin "4") (pinfunction "SSRX1+_4") (pintype "passive"))
    )
    (net (code "54") (name "unconnected-(IC1-SSRX1--Pad5)") (class "Default")
      (node (ref "IC1") (pin "5") (pinfunction "SSRX1-_5") (pintype "passive"))
    )
    (net (code "55") (name "unconnected-(IC1-SSRX2+-Pad71)") (class "Default")
      (node (ref "IC1") (pin "71") (pinfunction "SSRX2+_71") (pintype "passive"))
    )
    (net (code "56") (name "unconnected-(IC1-SSRX2--Pad72)") (class "Default")
      (node (ref "IC1") (pin "72") (pinfunction "SSRX2-_72") (pintype "passive"))
    )
    (net (code "57") (name "unconnected-(IC1-SSRX3+-Pad62)") (class "Default")
      (node (ref "IC1") (pin "62") (pinfunction "SSRX3+_62") (pintype "passive"))
    )
    (net (code "58") (name "unconnected-(IC1-SSRX3--Pad63)") (class "Default")
      (node (ref "IC1") (pin "63") (pinfunction "SSRX3-_63") (pintype "passive"))
    )
    (net (code "59") (name "unconnected-(IC1-SSRX4+-Pad13)") (class "Default")
      (node (ref "IC1") (pin "13") (pinfunction "SSRX4+_13") (pintype "passive"))
    )
    (net (code "60") (name "unconnected-(IC1-SSRX4--Pad14)") (class "Default")
      (node (ref "IC1") (pin "14") (pinfunction "SSRX4-_14") (pintype "passive"))
    )
    (net (code "61") (name "unconnected-(IC1-SSTX1+-Pad1)") (class "Default")
      (node (ref "IC1") (pin "1") (pinfunction "SSTX1+_1") (pintype "passive"))
    )
    (net (code "62") (name "unconnected-(IC1-SSTX1--Pad2)") (class "Default")
      (node (ref "IC1") (pin "2") (pinfunction "SSTX1-_2") (pintype "passive"))
    )
    (net (code "63") (name "unconnected-(IC1-SSTX2+-Pad68)") (class "Default")
      (node (ref "IC1") (pin "68") (pinfunction "SSTX2+_68") (pintype "passive"))
    )
    (net (code "64") (name "unconnected-(IC1-SSTX2--Pad69)") (class "Default")
      (node (ref "IC1") (pin "69") (pinfunction "SSTX2-_69") (pintype "passive"))
    )
    (net (code "65") (name "unconnected-(IC1-SSTX3+-Pad59)") (class "Default")
      (node (ref "IC1") (pin "59") (pinfunction "SSTX3+_59") (pintype "passive"))
    )
    (net (code "66") (name "unconnected-(IC1-SSTX3--Pad60)") (class "Default")
      (node (ref "IC1") (pin "60") (pinfunction "SSTX3-_60") (pintype "passive"))
    )
    (net (code "67") (name "unconnected-(IC1-SSTX4+-Pad10)") (class "Default")
      (node (ref "IC1") (pin "10") (pinfunction "SSTX4+_10") (pintype "passive"))
    )
    (net (code "68") (name "unconnected-(IC1-SSTX4--Pad11)") (class "Default")
      (node (ref "IC1") (pin "11") (pinfunction "SSTX4-_11") (pintype "passive"))
    )
  )
)
